# ESC_2S-5S.net
KiCad netlist of a schematic drawn in Altium Designer
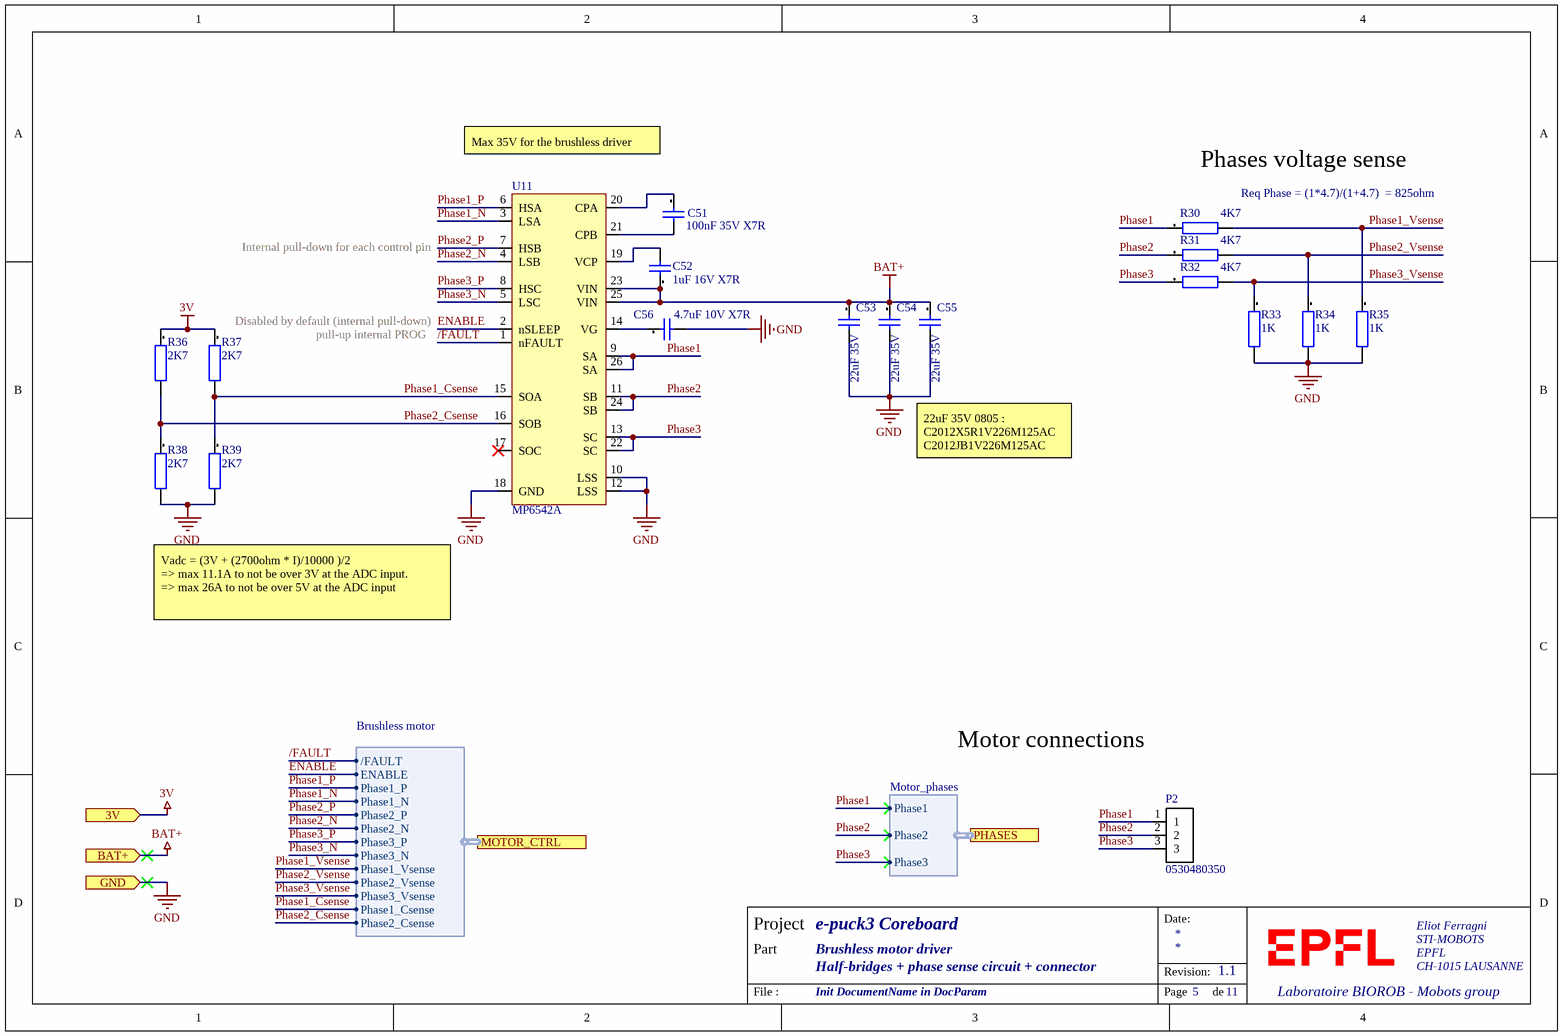
[diagram p0: ESC_2S-5S.SchDoc]

(export (version "E")
  (design (tool "Eeschema 10.0.6"))
  (components
    (comp (ref "C51")
      (value "100nF 35V X7R")
      (footprint "CAPC1005X05L")
      (description "Capacitor 0402")
      (libsource (lib "LSRO1Altium") (part "CAP-NP"))
    )
    (comp (ref "C52")
      (value "1uF 16V X7R")
      (footprint "CAPC1608X08L")
      (description "Capacitor 0603")
      (libsource (lib "LSRO1Altium") (part "CAP-NP"))
    )
    (comp (ref "C53")
      (value "22uF 35V")
      (footprint "CAPC2012X13L")
      (description "Capacitor 0805")
      (fields
        (field (name "MANUFACTURER") "TDK")
        (field (name "MANUFACTURER PART NUMBER") "C2012X5R1V226M125AC")
      )
      (libsource (lib "LSRO1Altium") (part "CAP-NP"))
    )
    (comp (ref "C54")
      (value "22uF 35V")
      (footprint "CAPC2012X13L")
      (description "Capacitor 0805")
      (fields
        (field (name "MANUFACTURER") "TDK")
        (field (name "MANUFACTURER PART NUMBER") "C2012X5R1V226M125AC")
      )
      (libsource (lib "LSRO1Altium") (part "CAP-NP"))
    )
    (comp (ref "C55")
      (value "22uF 35V")
      (footprint "CAPC2012X13L")
      (description "Capacitor 0805")
      (fields
        (field (name "MANUFACTURER") "TDK")
        (field (name "MANUFACTURER PART NUMBER") "C2012X5R1V226M125AC")
      )
      (libsource (lib "LSRO1Altium") (part "CAP-NP"))
    )
    (comp (ref "C56")
      (value "4.7uF 10V X7R")
      (footprint "CAPC2012X13L")
      (description "Capacitor 0805")
      (libsource (lib "LSRO1Altium") (part "CAP-NP"))
    )
    (comp (ref "P2")
      (value "0530480350")
      (footprint "0530480350")
      (description "CONN HEADER 3POS 1.25MM R/A TIN")
      (fields (field (name "MANUFACTURER") "Molex") (field (name "MANUFACTURER PART NUMBER") "0530480350"))
      (libsource (lib "Schlib") (part "0530480350"))
    )
    (comp (ref "R30")
      (value "4K7")
      (footprint "RESC0201(0603)_L")
      (description "Resistor 0201")
      (libsource (lib "LSRO1Altium") (part "RES"))
    )
    (comp (ref "R31")
      (value "4K7")
      (footprint "RESC0201(0603)_L")
      (description "Resistor 0201")
      (libsource (lib "LSRO1Altium") (part "RES"))
    )
    (comp (ref "R32")
      (value "4K7")
      (footprint "RESC0201(0603)_L")
      (description "Resistor 0201")
      (libsource (lib "LSRO1Altium") (part "RES"))
    )
    (comp (ref "R33")
      (value "1K")
      (footprint "RESC0201(0603)_L")
      (description "Resistor 0201")
      (libsource (lib "LSRO1Altium") (part "RES"))
    )
    (comp (ref "R34")
      (value "1K")
      (footprint "RESC0201(0603)_L")
      (description "Resistor 0201")
      (libsource (lib "LSRO1Altium") (part "RES"))
    )
    (comp (ref "R35")
      (value "1K")
      (footprint "RESC0201(0603)_L")
      (description "Resistor 0201")
      (libsource (lib "LSRO1Altium") (part "RES"))
    )
    (comp (ref "R36")
      (value "2K7")
      (footprint "RESC0201(0603)_L")
      (description "Resistor 0201")
      (libsource (lib "LSRO1Altium") (part "RES"))
    )
    (comp (ref "R37")
      (value "2K7")
      (footprint "RESC0201(0603)_L")
      (description "Resistor 0201")
      (libsource (lib "LSRO1Altium") (part "RES"))
    )
    (comp (ref "R38")
      (value "2K7")
      (footprint "RESC0201(0603)_L")
      (description "Resistor 0201")
      (libsource (lib "LSRO1Altium") (part "RES"))
    )
    (comp (ref "R39")
      (value "2K7")
      (footprint "RESC0201(0603)_L")
      (description "Resistor 0201")
      (libsource (lib "LSRO1Altium") (part "RES"))
    )
    (comp (ref "U11")
      (value "MP6542A")
      (footprint "FCQFN6x6-26")
      (description "11A integrated 3 half-bridges for brushless motor")
      (fields
        (field (name "MANUFACTURER") "Monolithic Power Systems")
        (field (name "MANUFACTURER PART NUMBER") "MP6542A")
      )
      (libsource (lib "Schlib") (part "MP6542A"))
    )
  )
  (nets
    (net (code "4") (name "/ENABLE") (class "Default")
      (node (ref "U11") (pin "2") (pinfunction "nSLEEP_2") (pintype "passive"))
    )
    (net (code "5") (name "/Phase1") (class "Default")
      (node (ref "P2") (pin "1") (pinfunction "1_1") (pintype "power_in"))
      (node (ref "R30") (pin "1") (pinfunction "1_1") (pintype "passive"))
      (node (ref "U11") (pin "26") (pinfunction "SA_26") (pintype "passive"))
      (node (ref "U11") (pin "9") (pinfunction "SA_9") (pintype "passive"))
    )
    (net (code "6") (name "/Phase1_Csense") (class "Default")
      (node (ref "R37") (pin "2") (pinfunction "2_2") (pintype "passive"))
      (node (ref "R39") (pin "1") (pinfunction "1_1") (pintype "passive"))
      (node (ref "U11") (pin "15") (pinfunction "SOA_15") (pintype "passive"))
    )
    (net (code "7") (name "/Phase1_N") (class "Default")
      (node (ref "U11") (pin "3") (pinfunction "LSA_3") (pintype "passive"))
    )
    (net (code "8") (name "/Phase1_P") (class "Default")
      (node (ref "U11") (pin "6") (pinfunction "HSA_6") (pintype "passive"))
    )
    (net (code "9") (name "/Phase1_Vsense") (class "Default")
      (node (ref "R30") (pin "2") (pinfunction "2_2") (pintype "passive"))
      (node (ref "R35") (pin "1") (pinfunction "1_1") (pintype "passive"))
    )
    (net (code "10") (name "/Phase2") (class "Default")
      (node (ref "P2") (pin "2") (pinfunction "2_2") (pintype "power_in"))
      (node (ref "R31") (pin "1") (pinfunction "1_1") (pintype "passive"))
      (node (ref "U11") (pin "11") (pinfunction "SB_11") (pintype "passive"))
      (node (ref "U11") (pin "24") (pinfunction "SB_24") (pintype "passive"))
    )
    (net (code "11") (name "/Phase2_Csense") (class "Default")
      (node (ref "R36") (pin "2") (pinfunction "2_2") (pintype "passive"))
      (node (ref "R38") (pin "1") (pinfunction "1_1") (pintype "passive"))
      (node (ref "U11") (pin "16") (pinfunction "SOB_16") (pintype "passive"))
    )
    (net (code "12") (name "/Phase2_N") (class "Default")
      (node (ref "U11") (pin "4") (pinfunction "LSB_4") (pintype "passive"))
    )
    (net (code "13") (name "/Phase2_P") (class "Default")
      (node (ref "U11") (pin "7") (pinfunction "HSB_7") (pintype "passive"))
    )
    (net (code "14") (name "/Phase2_Vsense") (class "Default")
      (node (ref "R31") (pin "2") (pinfunction "2_2") (pintype "passive"))
      (node (ref "R34") (pin "1") (pinfunction "1_1") (pintype "passive"))
    )
    (net (code "15") (name "/Phase3") (class "Default")
      (node (ref "P2") (pin "3") (pinfunction "3_3") (pintype "power_in"))
      (node (ref "R32") (pin "1") (pinfunction "1_1") (pintype "passive"))
      (node (ref "U11") (pin "13") (pinfunction "SC_13") (pintype "passive"))
      (node (ref "U11") (pin "22") (pinfunction "SC_22") (pintype "passive"))
    )
    (net (code "16") (name "/Phase3_N") (class "Default")
      (node (ref "U11") (pin "5") (pinfunction "LSC_5") (pintype "passive"))
    )
    (net (code "17") (name "/Phase3_P") (class "Default")
      (node (ref "U11") (pin "8") (pinfunction "HSC_8") (pintype "passive"))
    )
    (net (code "18") (name "/Phase3_Vsense") (class "Default")
      (node (ref "R32") (pin "2") (pinfunction "2_2") (pintype "passive"))
      (node (ref "R33") (pin "1") (pinfunction "1_1") (pintype "passive"))
    )
    (net (code "21") (name "/{slash}FAULT") (class "Default")
      (node (ref "U11") (pin "1") (pinfunction "nFAULT_1") (pintype "passive"))
    )
    (net (code "22") (name "3V") (class "Default")
      (node (ref "R36") (pin "1") (pinfunction "1_1") (pintype "passive"))
      (node (ref "R37") (pin "1") (pinfunction "1_1") (pintype "passive"))
    )
    (net (code "23") (name "BAT+") (class "Default")
      (node (ref "C52") (pin "1") (pinfunction "1_1") (pintype "passive"))
      (node (ref "C53") (pin "1") (pinfunction "1_1") (pintype "passive"))
      (node (ref "C54") (pin "1") (pinfunction "1_1") (pintype "passive"))
      (node (ref "C55") (pin "1") (pinfunction "1_1") (pintype "passive"))
      (node (ref "U11") (pin "23") (pinfunction "VIN_23") (pintype "passive"))
      (node (ref "U11") (pin "25") (pinfunction "VIN_25") (pintype "passive"))
    )
    (net (code "24") (name "GND") (class "Default")
      (node (ref "C53") (pin "2") (pinfunction "2_2") (pintype "passive"))
      (node (ref "C54") (pin "2") (pinfunction "2_2") (pintype "passive"))
      (node (ref "C55") (pin "2") (pinfunction "2_2") (pintype "passive"))
      (node (ref "C56") (pin "2") (pinfunction "2_2") (pintype "passive"))
      (node (ref "R33") (pin "2") (pinfunction "2_2") (pintype "passive"))
      (node (ref "R34") (pin "2") (pinfunction "2_2") (pintype "passive"))
      (node (ref "R35") (pin "2") (pinfunction "2_2") (pintype "passive"))
      (node (ref "R38") (pin "2") (pinfunction "2_2") (pintype "passive"))
      (node (ref "R39") (pin "2") (pinfunction "2_2") (pintype "passive"))
      (node (ref "U11") (pin "10") (pinfunction "LSS_10") (pintype "passive"))
      (node (ref "U11") (pin "12") (pinfunction "LSS_12") (pintype "passive"))
      (node (ref "U11") (pin "18") (pinfunction "GND_18") (pintype "passive"))
    )
    (net (code "25") (name "Net-(U11-CPA)") (class "Default")
      (node (ref "C51") (pin "1") (pinfunction "1_1") (pintype "passive"))
      (node (ref "U11") (pin "20") (pinfunction "CPA_20") (pintype "passive"))
    )
    (net (code "26") (name "Net-(U11-CPB)") (class "Default")
      (node (ref "C51") (pin "2") (pinfunction "2_2") (pintype "passive"))
      (node (ref "U11") (pin "21") (pinfunction "CPB_21") (pintype "passive"))
    )
    (net (code "27") (name "Net-(U11-VCP)") (class "Default")
      (node (ref "C52") (pin "2") (pinfunction "2_2") (pintype "passive"))
      (node (ref "U11") (pin "19") (pinfunction "VCP_19") (pintype "passive"))
    )
    (net (code "28") (name "Net-(U11-VG)") (class "Default")
      (node (ref "C56") (pin "1") (pinfunction "1_1") (pintype "passive"))
      (node (ref "U11") (pin "14") (pinfunction "VG_14") (pintype "passive"))
    )
    (net (code "29") (name "unconnected-(U11-SOC-Pad17)") (class "Default")
      (node (ref "U11") (pin "17") (pinfunction "SOC_17") (pintype "passive+no_connect"))
    )
  )
)
